# OpenRing_Debug.net
KiCad netlist of a schematic drawn in Altium Designer
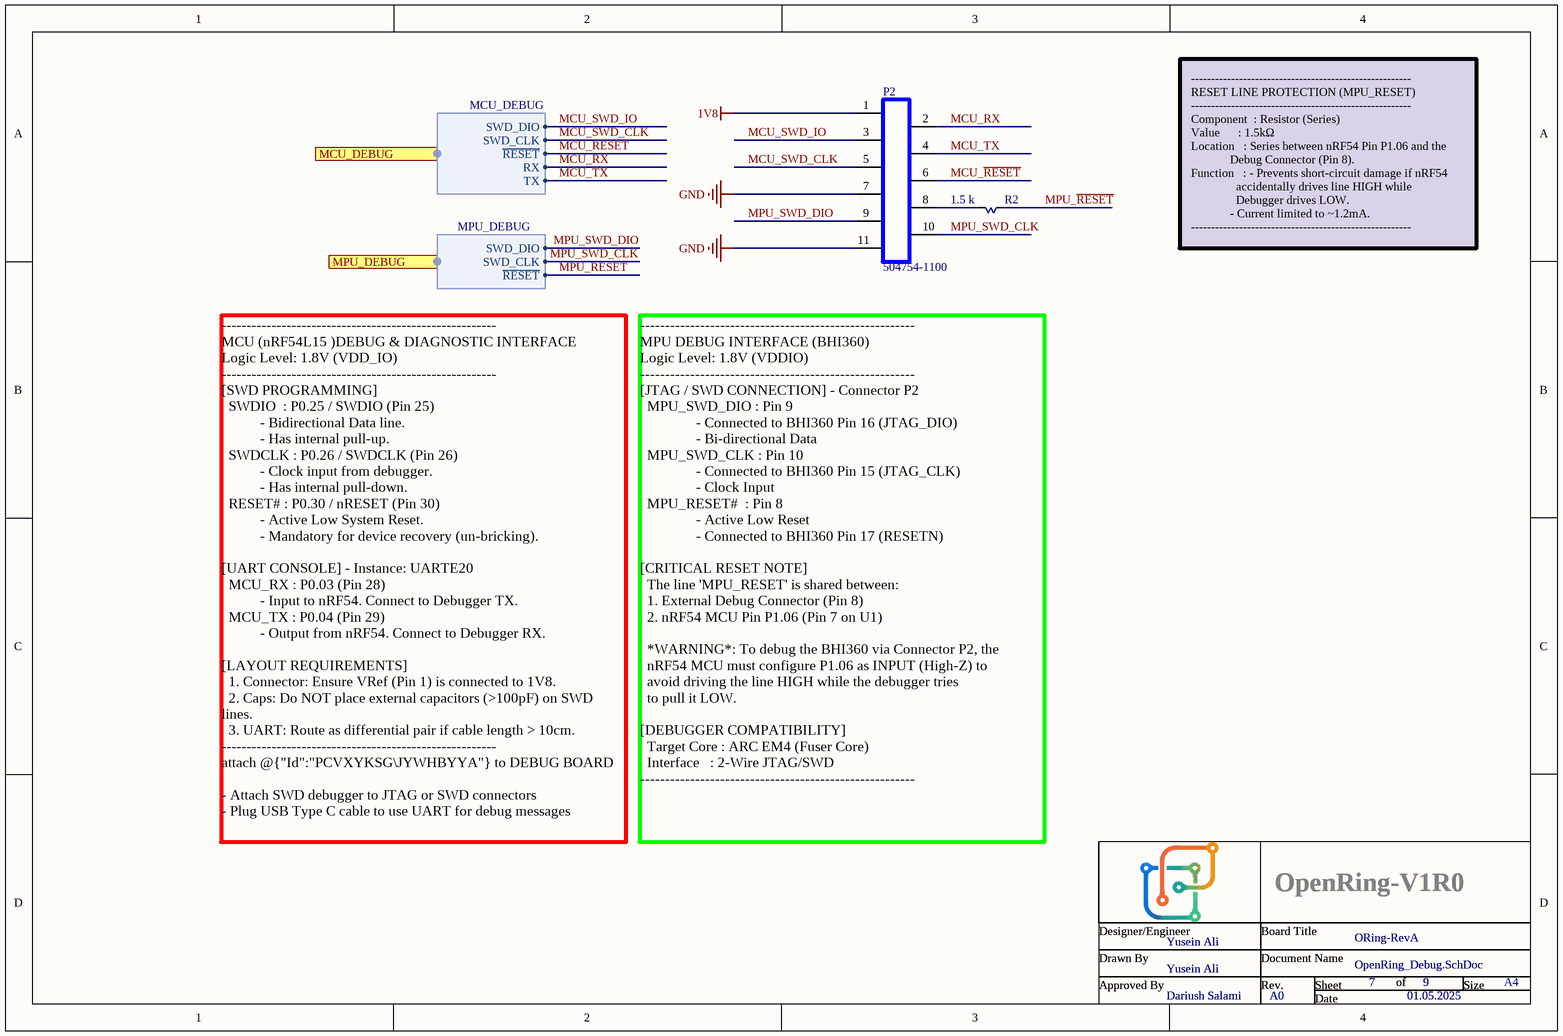
[diagram p0: OpenRing_Debug.SchDoc]

(export (version "E")
  (design (tool "Eeschema 10.0.6"))
  (components
    (comp (ref "P2")
      (value "504754-1100")
      (footprint "5047541100")
      (description "Conn FFC/FPC Connector SKT 11 POS 0.3mm Solder RA SMD Easy-On™ T/R")
      (fields (field (name "MANUFACTURER") "Molex") (field (name "CHECKED") "FALSE"))
      (libsource (lib "Connectors") (part "504754-1100"))
    )
    (comp (ref "R2")
      (value "1.5 k")
      (footprint "RESC1005X04N")
      (description "RES SMD 1.5K OHM 1% 1/10W 0402")
      (fields
        (field (name "MANUFACTURER") "Panasonic Electronic Components")
        (field (name "MANUFACTURER PART NUMBER") "ERJ-2RKF1501X")
      )
      (libsource (lib "OpenRingComponents") (part "ERJ-2RKF1501X"))
    )
  )
  (nets
    (net (code "3") (name "/MCU_RX") (class "Default")
      (node (ref "P2") (pin "2") (pinfunction "2_2") (pintype "passive"))
    )
    (net (code "4") (name "/MCU_SWD_CLK") (class "Default")
      (node (ref "P2") (pin "5") (pinfunction "5_5") (pintype "passive"))
    )
    (net (code "5") (name "/MCU_SWD_IO") (class "Default")
      (node (ref "P2") (pin "3") (pinfunction "3_3") (pintype "passive"))
    )
    (net (code "6") (name "/MCU_TX") (class "Default")
      (node (ref "P2") (pin "4") (pinfunction "4_4") (pintype "passive"))
    )
    (net (code "7") (name "/MCU_~{RESET}") (class "Default")
      (node (ref "P2") (pin "6") (pinfunction "6_6") (pintype "passive"))
    )
    (net (code "8") (name "/MPU_SWD_CLK") (class "Default")
      (node (ref "P2") (pin "10") (pinfunction "10_10") (pintype "passive"))
    )
    (net (code "9") (name "/MPU_SWD_DIO") (class "Default")
      (node (ref "P2") (pin "9") (pinfunction "9_9") (pintype "passive"))
    )
    (net (code "10") (name "/MPU_~{RESET}") (class "Default")
      (node (ref "R2") (pin "1") (pinfunction "1_1") (pintype "passive"))
    )
    (net (code "13") (name "1V8") (class "Default")
      (node (ref "P2") (pin "1") (pinfunction "1_1") (pintype "passive"))
    )
    (net (code "14") (name "GND") (class "Default")
      (node (ref "P2") (pin "11") (pinfunction "11_11") (pintype "passive"))
      (node (ref "P2") (pin "7") (pinfunction "7_7") (pintype "passive"))
    )
    (net (code "15") (name "Net-(P2-Pad8)") (class "Default")
      (node (ref "P2") (pin "8") (pinfunction "8_8") (pintype "passive"))
      (node (ref "R2") (pin "2") (pinfunction "2_2") (pintype "passive"))
    )
  )
)
